# BSPD_rev11_clean.net
KiCad netlist of a schematic drawn in EAGLE
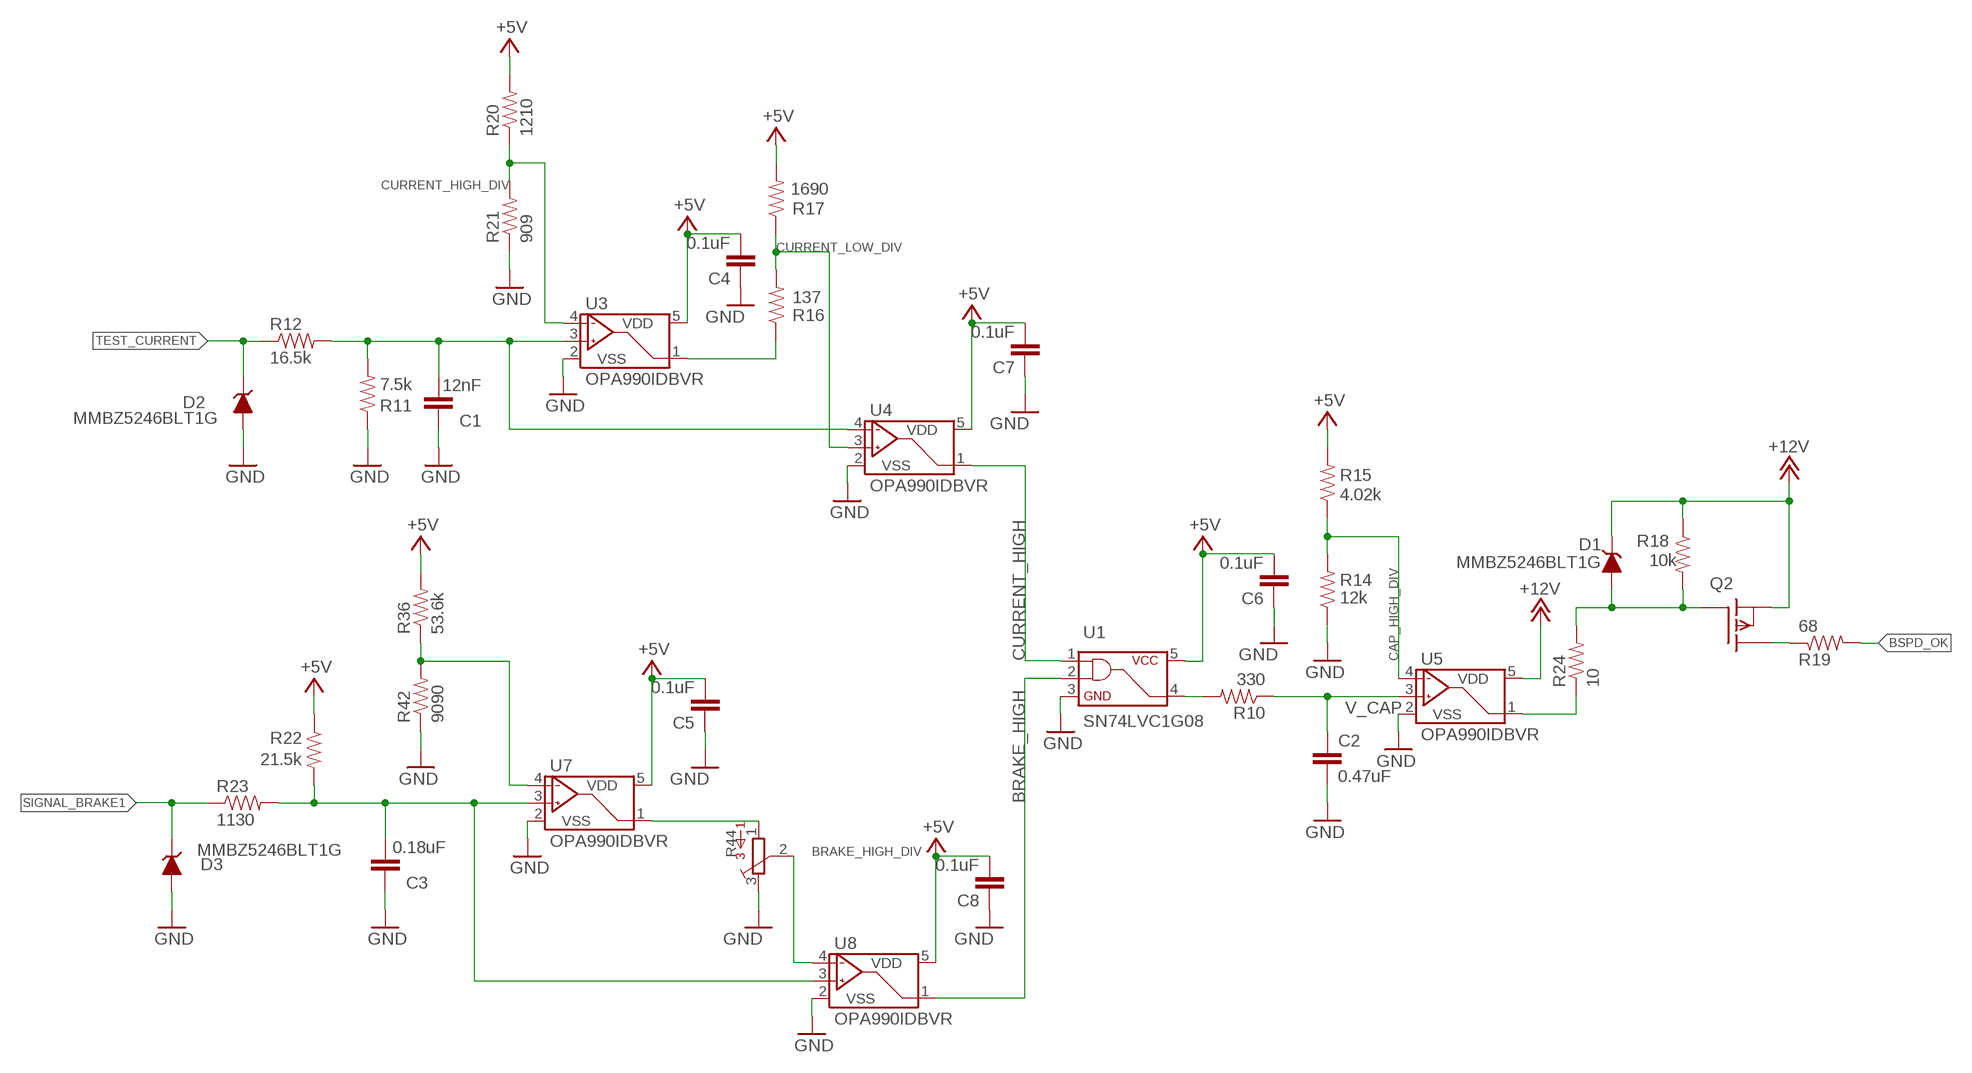
[diagram p0: schematic, sheet 1]

(export (version "E")
  (design (tool "Eeschema 10.0.6"))
  (components
    (comp (ref "C1")
      (value "12nF")
      (footprint "eagle-import:0603-CAP")
      (libsource (lib "eagle-import") (part "CAP0603-CAP"))
    )
    (comp (ref "C2")
      (value "0.47uF")
      (footprint "eagle-import:0603-CAP")
      (libsource (lib "eagle-import") (part "CAP0603-CAP"))
    )
    (comp (ref "C3")
      (value "0.18uF")
      (footprint "eagle-import:0603-CAP")
      (libsource (lib "eagle-import") (part "CAP0603-CAP"))
    )
    (comp (ref "C4")
      (value "0.1uF")
      (footprint "eagle-import:0603-CAP")
      (libsource (lib "eagle-import") (part "CAP0603-CAP"))
    )
    (comp (ref "C5")
      (value "0.1uF")
      (footprint "eagle-import:0603-CAP")
      (libsource (lib "eagle-import") (part "CAP0603-CAP"))
    )
    (comp (ref "C6")
      (value "0.1uF")
      (footprint "eagle-import:0603-CAP")
      (libsource (lib "eagle-import") (part "CAP0603-CAP"))
    )
    (comp (ref "C7")
      (value "0.1uF")
      (footprint "eagle-import:0603-CAP")
      (libsource (lib "eagle-import") (part "CAP0603-CAP"))
    )
    (comp (ref "C8")
      (value "0.1uF")
      (footprint "eagle-import:0603-CAP")
      (libsource (lib "eagle-import") (part "CAP0603-CAP"))
    )
    (comp (ref "D1")
      (value "MMBZ5246BLT1G")
      (footprint "eagle-import:SOT23")
      (libsource (lib "eagle-import") (part "DIODE_ZENER"))
    )
    (comp (ref "D2")
      (value "MMBZ5246BLT1G")
      (footprint "eagle-import:SOT23")
      (libsource (lib "eagle-import") (part "DIODE_ZENER"))
    )
    (comp (ref "D3")
      (value "MMBZ5246BLT1G")
      (footprint "eagle-import:SOT23")
      (libsource (lib "eagle-import") (part "DIODE_ZENER"))
    )
    (comp (ref "Q2")
      (value "P-CHANNEL_MOSFET_DMP3099L-7")
      (footprint "eagle-import:SOT23")
      (libsource (lib "eagle-import") (part "P-CHANNEL_MOSFET_DMP3099L-7"))
    )
    (comp (ref "R10")
      (value "330")
      (footprint "eagle-import:0603-RES")
      (libsource (lib "eagle-import") (part "RESISTOR0603"))
    )
    (comp (ref "R11")
      (value "7.5k")
      (footprint "eagle-import:0603-RES")
      (libsource (lib "eagle-import") (part "RESISTOR0603"))
    )
    (comp (ref "R12")
      (value "16.5k")
      (footprint "eagle-import:0603-RES")
      (libsource (lib "eagle-import") (part "RESISTOR0603"))
    )
    (comp (ref "R14")
      (value "12k")
      (footprint "eagle-import:0603-RES")
      (libsource (lib "eagle-import") (part "RESISTOR0603"))
    )
    (comp (ref "R15")
      (value "4.02k")
      (footprint "eagle-import:0603-RES")
      (libsource (lib "eagle-import") (part "RESISTOR0603"))
    )
    (comp (ref "R16")
      (value "137")
      (footprint "eagle-import:0603-RES")
      (libsource (lib "eagle-import") (part "RESISTOR0603"))
    )
    (comp (ref "R17")
      (value "1690")
      (footprint "eagle-import:0603-RES")
      (libsource (lib "eagle-import") (part "RESISTOR0603"))
    )
    (comp (ref "R18")
      (value "10k")
      (footprint "eagle-import:0603-RES")
      (libsource (lib "eagle-import") (part "RESISTOR0603"))
    )
    (comp (ref "R19")
      (value "68")
      (footprint "eagle-import:0603-RES")
      (libsource (lib "eagle-import") (part "RESISTOR0603"))
    )
    (comp (ref "R20")
      (value "1210")
      (footprint "eagle-import:0603-RES")
      (libsource (lib "eagle-import") (part "RESISTOR0603"))
    )
    (comp (ref "R21")
      (value "909")
      (footprint "eagle-import:0603-RES")
      (libsource (lib "eagle-import") (part "RESISTOR0603"))
    )
    (comp (ref "R22")
      (value "21.5k")
      (footprint "eagle-import:0603-RES")
      (libsource (lib "eagle-import") (part "RESISTOR0603"))
    )
    (comp (ref "R23")
      (value "1130")
      (footprint "eagle-import:0603-RES")
      (libsource (lib "eagle-import") (part "RESISTOR0603"))
    )
    (comp (ref "R24")
      (value "10")
      (footprint "eagle-import:0603-RES")
      (libsource (lib "eagle-import") (part "RESISTOR0603"))
    )
    (comp (ref "R36")
      (value "53.6k")
      (footprint "eagle-import:0603-RES")
      (libsource (lib "eagle-import") (part "RESISTOR0603"))
    )
    (comp (ref "R42")
      (value "9090")
      (footprint "eagle-import:0603-RES")
      (libsource (lib "eagle-import") (part "RESISTOR0603"))
    )
    (comp (ref "R44")
      (value "TRIMPOT_3296C")
      (footprint "eagle-import:TRIMPOT_3296")
      (libsource (lib "eagle-import") (part "TRIMPOT_3296C"))
    )
    (comp (ref "U1")
      (value "SN74LVC1G08")
      (footprint "eagle-import:SOT-23-5")
      (libsource (lib "eagle-import") (part "SN74LVC1G08"))
    )
    (comp (ref "U3")
      (value "OPA990IDBVR")
      (footprint "eagle-import:SOT-23-5")
      (libsource (lib "eagle-import") (part "OPA990IDBVR"))
    )
    (comp (ref "U4")
      (value "OPA990IDBVR")
      (footprint "eagle-import:SOT-23-5")
      (libsource (lib "eagle-import") (part "OPA990IDBVR"))
    )
    (comp (ref "U5")
      (value "OPA990IDBVR")
      (footprint "eagle-import:SOT-23-5")
      (libsource (lib "eagle-import") (part "OPA990IDBVR"))
    )
    (comp (ref "U7")
      (value "OPA990IDBVR")
      (footprint "eagle-import:SOT-23-5")
      (libsource (lib "eagle-import") (part "OPA990IDBVR"))
    )
    (comp (ref "U8")
      (value "OPA990IDBVR")
      (footprint "eagle-import:SOT-23-5")
      (libsource (lib "eagle-import") (part "OPA990IDBVR"))
    )
  )
  (nets
    (net (code "1") (name "+5V") (class "Default")
      (node (ref "C4") (pin "2") (pinfunction "2_2") (pintype "passive"))
      (node (ref "C5") (pin "2") (pinfunction "2_2") (pintype "passive"))
      (node (ref "C6") (pin "2") (pinfunction "2_2") (pintype "passive"))
      (node (ref "C7") (pin "2") (pinfunction "2_2") (pintype "passive"))
      (node (ref "C8") (pin "2") (pinfunction "2_2") (pintype "passive"))
      (node (ref "R15") (pin "2") (pinfunction "2_2") (pintype "passive"))
      (node (ref "R17") (pin "2") (pinfunction "2_2") (pintype "passive"))
      (node (ref "R20") (pin "2") (pinfunction "2_2") (pintype "passive"))
      (node (ref "R22") (pin "1") (pinfunction "1_1") (pintype "passive"))
      (node (ref "R36") (pin "2") (pinfunction "2_2") (pintype "passive"))
      (node (ref "U1") (pin "5") (pinfunction "5_5") (pintype "passive"))
      (node (ref "U3") (pin "5") (pinfunction "VDD_5") (pintype "passive"))
      (node (ref "U4") (pin "5") (pinfunction "VDD_5") (pintype "passive"))
      (node (ref "U7") (pin "5") (pinfunction "VDD_5") (pintype "passive"))
      (node (ref "U8") (pin "5") (pinfunction "VDD_5") (pintype "passive"))
    )
    (net (code "2") (name "+12V") (class "Default")
      (node (ref "D1") (pin "3") (pinfunction "C_3") (pintype "passive"))
      (node (ref "Q2") (pin "2") (pinfunction "S_2") (pintype "passive"))
      (node (ref "R18") (pin "1") (pinfunction "1_1") (pintype "passive"))
      (node (ref "U5") (pin "5") (pinfunction "VDD_5") (pintype "passive"))
    )
    (net (code "3") (name "/BRAKE_HIGH") (class "Default")
      (node (ref "U1") (pin "2") (pinfunction "2_2") (pintype "passive"))
      (node (ref "U8") (pin "1") (pinfunction "VOUT_1") (pintype "passive"))
    )
    (net (code "4") (name "/BRAKE_HIGH_DIV") (class "Default")
      (node (ref "R44") (pin "2") (pinfunction "2_2") (pintype "passive"))
      (node (ref "U8") (pin "4") (pinfunction "VIN-_4") (pintype "passive"))
    )
    (net (code "5") (name "/CAP_HIGH_DIV") (class "Default")
      (node (ref "R14") (pin "2") (pinfunction "2_2") (pintype "passive"))
      (node (ref "R15") (pin "1") (pinfunction "1_1") (pintype "passive"))
      (node (ref "U5") (pin "4") (pinfunction "VIN-_4") (pintype "passive"))
    )
    (net (code "6") (name "/CURRENT_HIGH") (class "Default")
      (node (ref "U1") (pin "1") (pinfunction "1_1") (pintype "passive"))
      (node (ref "U4") (pin "1") (pinfunction "VOUT_1") (pintype "passive"))
    )
    (net (code "7") (name "/CURRENT_HIGH_DIV") (class "Default")
      (node (ref "R20") (pin "1") (pinfunction "1_1") (pintype "passive"))
      (node (ref "R21") (pin "2") (pinfunction "2_2") (pintype "passive"))
      (node (ref "U3") (pin "4") (pinfunction "VIN-_4") (pintype "passive"))
    )
    (net (code "8") (name "/CURRENT_LOW_DIV") (class "Default")
      (node (ref "R16") (pin "2") (pinfunction "2_2") (pintype "passive"))
      (node (ref "R17") (pin "1") (pinfunction "1_1") (pintype "passive"))
      (node (ref "U4") (pin "3") (pinfunction "VIN+_3") (pintype "passive"))
    )
    (net (code "9") (name "/V_CAP") (class "Default")
      (node (ref "C2") (pin "1") (pinfunction "1_1") (pintype "passive"))
      (node (ref "R10") (pin "1") (pinfunction "1_1") (pintype "passive"))
      (node (ref "U5") (pin "3") (pinfunction "VIN+_3") (pintype "passive"))
    )
    (net (code "10") (name "BSPD_OK") (class "Default")
      (node (ref "R19") (pin "2") (pinfunction "2_2") (pintype "passive"))
    )
    (net (code "11") (name "GND") (class "Default")
      (node (ref "C1") (pin "1") (pinfunction "1_1") (pintype "passive"))
      (node (ref "C2") (pin "2") (pinfunction "2_2") (pintype "passive"))
      (node (ref "C3") (pin "1") (pinfunction "1_1") (pintype "passive"))
      (node (ref "C4") (pin "1") (pinfunction "1_1") (pintype "passive"))
      (node (ref "C5") (pin "1") (pinfunction "1_1") (pintype "passive"))
      (node (ref "C6") (pin "1") (pinfunction "1_1") (pintype "passive"))
      (node (ref "C7") (pin "1") (pinfunction "1_1") (pintype "passive"))
      (node (ref "C8") (pin "1") (pinfunction "1_1") (pintype "passive"))
      (node (ref "D2") (pin "1") (pinfunction "A_1") (pintype "passive"))
      (node (ref "D3") (pin "1") (pinfunction "A_1") (pintype "passive"))
      (node (ref "R11") (pin "1") (pinfunction "1_1") (pintype "passive"))
      (node (ref "R14") (pin "1") (pinfunction "1_1") (pintype "passive"))
      (node (ref "R21") (pin "1") (pinfunction "1_1") (pintype "passive"))
      (node (ref "R42") (pin "1") (pinfunction "1_1") (pintype "passive"))
      (node (ref "R44") (pin "3") (pinfunction "3_3") (pintype "passive"))
      (node (ref "U1") (pin "3") (pinfunction "3_3") (pintype "passive"))
      (node (ref "U3") (pin "2") (pinfunction "VSS_2") (pintype "passive"))
      (node (ref "U4") (pin "2") (pinfunction "VSS_2") (pintype "passive"))
      (node (ref "U5") (pin "2") (pinfunction "VSS_2") (pintype "passive"))
      (node (ref "U7") (pin "2") (pinfunction "VSS_2") (pintype "passive"))
      (node (ref "U8") (pin "2") (pinfunction "VSS_2") (pintype "passive"))
    )
    (net (code "12") (name "Net-(D1-A)") (class "Default")
      (node (ref "D1") (pin "1") (pinfunction "A_1") (pintype "passive"))
      (node (ref "Q2") (pin "1") (pinfunction "G_1") (pintype "passive"))
      (node (ref "R18") (pin "2") (pinfunction "2_2") (pintype "passive"))
      (node (ref "R24") (pin "2") (pinfunction "2_2") (pintype "passive"))
    )
    (net (code "13") (name "Net-(Q2-D)") (class "Default")
      (node (ref "Q2") (pin "3") (pinfunction "D_3") (pintype "passive"))
      (node (ref "R19") (pin "1") (pinfunction "1_1") (pintype "passive"))
    )
    (net (code "14") (name "Net-(R10-Pad2)") (class "Default")
      (node (ref "R10") (pin "2") (pinfunction "2_2") (pintype "passive"))
      (node (ref "U1") (pin "4") (pinfunction "4_4") (pintype "passive"))
    )
    (net (code "15") (name "Net-(U3-VIN+)") (class "Default")
      (node (ref "C1") (pin "2") (pinfunction "2_2") (pintype "passive"))
      (node (ref "R11") (pin "2") (pinfunction "2_2") (pintype "passive"))
      (node (ref "R12") (pin "2") (pinfunction "2_2") (pintype "passive"))
      (node (ref "U3") (pin "3") (pinfunction "VIN+_3") (pintype "passive"))
      (node (ref "U4") (pin "4") (pinfunction "VIN-_4") (pintype "passive"))
    )
    (net (code "16") (name "Net-(U3-VOUT)") (class "Default")
      (node (ref "R16") (pin "1") (pinfunction "1_1") (pintype "passive"))
      (node (ref "U3") (pin "1") (pinfunction "VOUT_1") (pintype "passive"))
    )
    (net (code "17") (name "Net-(U5-VOUT)") (class "Default")
      (node (ref "R24") (pin "1") (pinfunction "1_1") (pintype "passive"))
      (node (ref "U5") (pin "1") (pinfunction "VOUT_1") (pintype "passive"))
    )
    (net (code "18") (name "Net-(U7-VIN+)") (class "Default")
      (node (ref "C3") (pin "2") (pinfunction "2_2") (pintype "passive"))
      (node (ref "R22") (pin "2") (pinfunction "2_2") (pintype "passive"))
      (node (ref "R23") (pin "2") (pinfunction "2_2") (pintype "passive"))
      (node (ref "U7") (pin "3") (pinfunction "VIN+_3") (pintype "passive"))
      (node (ref "U8") (pin "3") (pinfunction "VIN+_3") (pintype "passive"))
    )
    (net (code "19") (name "Net-(U7-VIN-)") (class "Default")
      (node (ref "R36") (pin "1") (pinfunction "1_1") (pintype "passive"))
      (node (ref "R42") (pin "2") (pinfunction "2_2") (pintype "passive"))
      (node (ref "U7") (pin "4") (pinfunction "VIN-_4") (pintype "passive"))
    )
    (net (code "20") (name "Net-(U7-VOUT)") (class "Default")
      (node (ref "R44") (pin "1") (pinfunction "1_1") (pintype "passive"))
      (node (ref "U7") (pin "1") (pinfunction "VOUT_1") (pintype "passive"))
    )
    (net (code "21") (name "SIGNAL_BRAKE1") (class "Default")
      (node (ref "D3") (pin "3") (pinfunction "C_3") (pintype "passive"))
      (node (ref "R23") (pin "1") (pinfunction "1_1") (pintype "passive"))
    )
    (net (code "22") (name "TEST_CURRENT") (class "Default")
      (node (ref "D2") (pin "3") (pinfunction "C_3") (pintype "passive"))
      (node (ref "R12") (pin "1") (pinfunction "1_1") (pintype "passive"))
    )
  )
)
